# Cortex_Ports.net
KiCad netlist of a schematic drawn in Altium Designer
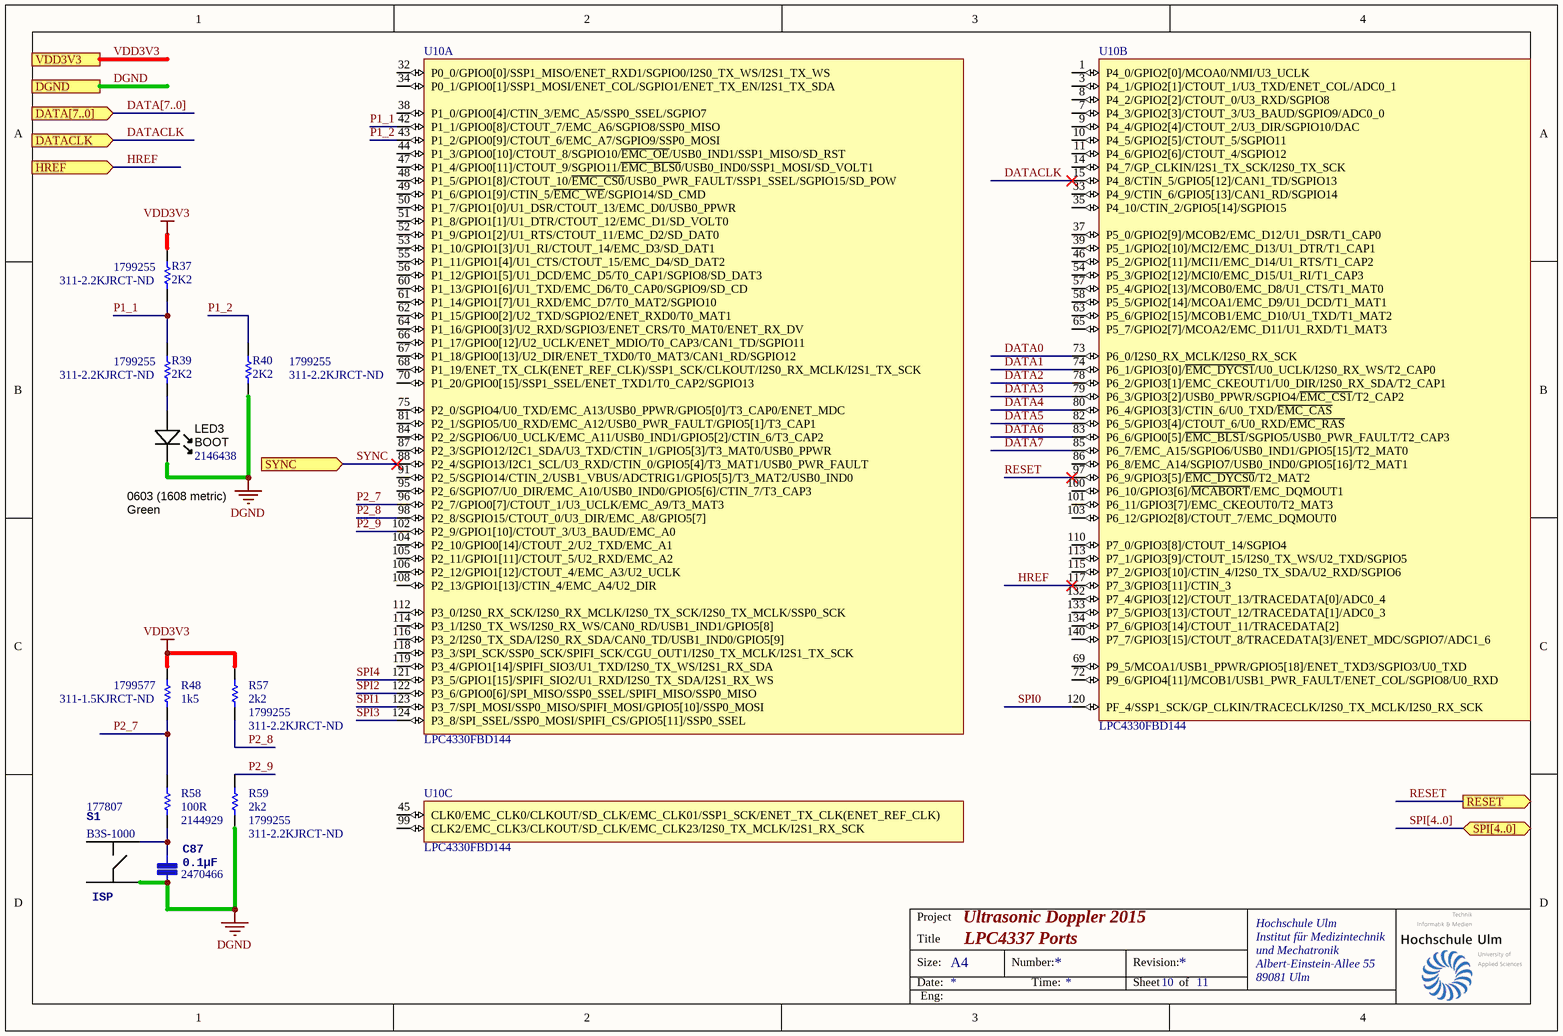
[diagram p0: Cortex_Ports.SchDoc]

(export (version "E")
  (design (tool "Eeschema 10.0.6"))
  (components
    (comp (ref "C87")
      (value "0.1µF")
      (footprint "0402[1005]")
      (description "Cap")
      (fields (field (name "SUPPLIER PART NUMBER 1") "2470466"))
      (libsource (lib "Components") (part "Capacitor"))
    )
    (comp (ref "LED3")
      (value "BOOT")
      (footprint "LED-0603-GREEN")
      (description "LED 0603 SMD Green 525nm 350mcd 20mA")
      (fields
        (field (name "PACKAGE / CASE") "0603 (1608 metric)")
        (field (name "COLOR") "Green")
        (field (name "SUPPLIER PART NUMBER 1") "2146438")
      )
      (libsource (lib "USD Parts") (part "LED_SMD_Green_0603_525nm_350mcd"))
    )
    (comp (ref "R37")
      (value "2K2")
      (footprint "0402[1005]")
      (description "Resistor")
      (fields
        (field (name "SUPPLIER PART NUMBER 1") "311-2.2KJRCT-ND")
        (field (name "SUPPLIER PART NUMBER 2") "1799255")
        (field (name "PUBLISHER") "Altium Limited")
      )
      (libsource (lib "Components") (part "Resistor"))
    )
    (comp (ref "R39")
      (value "2K2")
      (footprint "0402[1005]")
      (description "Resistor")
      (fields
        (field (name "SUPPLIER PART NUMBER 1") "311-2.2KJRCT-ND")
        (field (name "SUPPLIER PART NUMBER 2") "1799255")
        (field (name "PUBLISHER") "Altium Limited")
      )
      (libsource (lib "Components") (part "Resistor"))
    )
    (comp (ref "R40")
      (value "2K2")
      (footprint "0402[1005]")
      (description "Resistor")
      (fields
        (field (name "SUPPLIER PART NUMBER 1") "311-2.2KJRCT-ND")
        (field (name "SUPPLIER PART NUMBER 2") "1799255")
        (field (name "PUBLISHER") "Altium Limited")
      )
      (libsource (lib "Components") (part "Resistor"))
    )
    (comp (ref "R48")
      (value "1k5")
      (footprint "0402[1005]")
      (description "Resistor")
      (fields
        (field (name "SUPPLIER PART NUMBER 1") "311-1.5KJRCT-ND")
        (field (name "SUPPLIER PART NUMBER 2") "1799577")
        (field (name "PUBLISHER") "Altium Limited")
      )
      (libsource (lib "Components") (part "Resistor"))
    )
    (comp (ref "R57")
      (value "2k2")
      (footprint "0402[1005]")
      (description "Resistor")
      (fields
        (field (name "SUPPLIER PART NUMBER 1") "311-2.2KJRCT-ND")
        (field (name "SUPPLIER PART NUMBER 2") "1799255")
        (field (name "PUBLISHER") "Altium Limited")
      )
      (libsource (lib "Components") (part "Resistor"))
    )
    (comp (ref "R58")
      (value "100R")
      (footprint "0402[1005]")
      (description "Resistor")
      (fields (field (name "SUPPLIER PART NUMBER 1") "2144929") (field (name "PUBLISHER") "Altium Limited"))
      (libsource (lib "Components") (part "Resistor"))
    )
    (comp (ref "R59")
      (value "2k2")
      (footprint "0402[1005]")
      (description "Resistor")
      (fields
        (field (name "SUPPLIER PART NUMBER 1") "311-2.2KJRCT-ND")
        (field (name "SUPPLIER PART NUMBER 2") "1799255")
        (field (name "PUBLISHER") "Altium Limited")
      )
      (libsource (lib "Components") (part "Resistor"))
    )
    (comp (ref "S1")
      (value "ISP")
      (footprint "Omron B3S1000")
      (description "Sealed Tactile Switch (SMT)")
      (fields (field (name "ALTIUM_VALUE") "B3S-1000") (field (name "SUPPLIER PART NUMBER 1") "177807"))
      (libsource (lib "USD Parts") (part "B3S-1000"))
    )
    (comp (ref "U10")
      (value "LPC4330FBD144")
      (footprint "LQFP144")
      (libsource (lib "USD Parts") (part "LPC4330FBD144"))
    )
  )
  (nets
    (net (code "1") (name "/DATA0") (class "Default")
      (node (ref "U10") (pin "73") (pinfunction "P6_0/I2S0_RX_MCLK/I2S0_RX_SCK_73") (pintype "bidirectional"))
    )
    (net (code "2") (name "/DATA1") (class "Default")
      (node (ref "U10") (pin "74") (pinfunction "P6_1/GPIO3[0]/~{EMC_DYCS1}/U0_UCLK/I2S0_RX_WS/T2_CAP0_74") (pintype "bidirectional"))
    )
    (net (code "3") (name "/DATA2") (class "Default")
      (node (ref "U10") (pin "78") (pinfunction "P6_2/GPIO3[1]/EMC_CKEOUT1/U0_DIR/I2S0_RX_SDA/T2_CAP1_78") (pintype "bidirectional"))
    )
    (net (code "4") (name "/DATA3") (class "Default")
      (node (ref "U10") (pin "79") (pinfunction "P6_3/GPIO3[2]/USB0_PPWR/SGPIO4/~{EMC_CS1}/T2_CAP2_79") (pintype "bidirectional"))
    )
    (net (code "5") (name "/DATA4") (class "Default")
      (node (ref "U10") (pin "80") (pinfunction "P6_4/GPIO3[3]/CTIN_6/U0_TXD/~{EMC_CAS}_80") (pintype "bidirectional"))
    )
    (net (code "6") (name "/DATA5") (class "Default")
      (node (ref "U10") (pin "82") (pinfunction "P6_5/GPIO3[4]/CTOUT_6/U0_RXD/~{EMC_RAS}_82") (pintype "bidirectional"))
    )
    (net (code "7") (name "/DATA6") (class "Default")
      (node (ref "U10") (pin "83") (pinfunction "P6_6/GPIO0[5]/~{EMC_BLS1}/SGPIO5/USB0_PWR_FAULT/T2_CAP3_83") (pintype "bidirectional"))
    )
    (net (code "8") (name "/DATA7") (class "Default")
      (node (ref "U10") (pin "85") (pinfunction "P6_7/EMC_A15/SGPIO6/USB0_IND1/GPIO5[15]/T2_MAT0_85") (pintype "bidirectional"))
    )
    (net (code "9") (name "/DATACLK") (class "Default")
      (node (ref "U10") (pin "15") (pinfunction "P4_8/CTIN_5/GPIO5[12]/CAN1_TD/SGPIO13_15") (pintype "bidirectional+no_connect"))
    )
    (net (code "11") (name "/HREF") (class "Default")
      (node (ref "U10") (pin "117") (pinfunction "P7_3/GPIO3[11]/CTIN_3_117") (pintype "bidirectional+no_connect"))
    )
    (net (code "12") (name "/P1_1") (class "Default")
      (node (ref "R37") (pin "1") (pinfunction "1_1") (pintype "passive"))
      (node (ref "R39") (pin "1") (pinfunction "1_1") (pintype "passive"))
      (node (ref "U10") (pin "42") (pinfunction "P1_1/GPIO0[8]/CTOUT_7/EMC_A6/SGPIO8/SSP0_MISO_42") (pintype "bidirectional"))
    )
    (net (code "13") (name "/P1_2") (class "Default")
      (node (ref "R40") (pin "1") (pinfunction "1_1") (pintype "passive"))
      (node (ref "U10") (pin "43") (pinfunction "P1_2/GPIO0[9]/CTOUT_6/EMC_A7/SGPIO9/SSP0_MOSI_43") (pintype "bidirectional"))
    )
    (net (code "14") (name "/P2_7") (class "Default")
      (node (ref "R48") (pin "2") (pinfunction "2_2") (pintype "passive"))
      (node (ref "R58") (pin "1") (pinfunction "1_1") (pintype "passive"))
      (node (ref "U10") (pin "96") (pinfunction "P2_7/GPIO0[7]/CTOUT_1/U3_UCLK/EMC_A9/T3_MAT3_96") (pintype "bidirectional"))
    )
    (net (code "15") (name "/P2_8") (class "Default")
      (node (ref "R57") (pin "2") (pinfunction "2_2") (pintype "passive"))
      (node (ref "U10") (pin "98") (pinfunction "P2_8/SGPIO15/CTOUT_0/U3_DIR/EMC_A8/GPIO5[7]_98") (pintype "bidirectional"))
    )
    (net (code "16") (name "/P2_9") (class "Default")
      (node (ref "R59") (pin "1") (pinfunction "1_1") (pintype "passive"))
      (node (ref "U10") (pin "102") (pinfunction "P2_9/GPIO1[10]/CTOUT_3/U3_BAUD/EMC_A0_102") (pintype "bidirectional"))
    )
    (net (code "17") (name "/RESET") (class "Default")
      (node (ref "U10") (pin "97") (pinfunction "P6_9/GPIO3[5]/~{EMC_DYCS0}/T2_MAT2_97") (pintype "bidirectional"))
    )
    (net (code "18") (name "/SPI0") (class "Default")
      (node (ref "U10") (pin "120") (pinfunction "PF_4/SSP1_SCK/GP_CLKIN/TRACECLK/I2S0_TX_MCLK/I2S0_RX_SCK_120") (pintype "bidirectional"))
    )
    (net (code "19") (name "/SPI1") (class "Default")
      (node (ref "U10") (pin "123") (pinfunction "P3_7/SPI_MOSI/SSP0_MISO/SPIFI_MOSI/GPIO5[10]/SSP0_MOSI_123") (pintype "bidirectional"))
    )
    (net (code "20") (name "/SPI2") (class "Default")
      (node (ref "U10") (pin "122") (pinfunction "P3_6/GPIO0[6]/SPI_MISO/SSP0_SSEL/SPIFI_MISO/SSP0_MISO_122") (pintype "bidirectional"))
    )
    (net (code "21") (name "/SPI3") (class "Default")
      (node (ref "U10") (pin "124") (pinfunction "P3_8/SPI_SSEL/SSP0_MOSI/SPIFI_CS/GPIO5[11]/SSP0_SSEL_124") (pintype "bidirectional"))
    )
    (net (code "22") (name "/SPI4") (class "Default")
      (node (ref "U10") (pin "121") (pinfunction "P3_5/GPIO1[15]/SPIFI_SIO2/U1_RXD/I2S0_TX_SDA/I2S1_RX_WS_121") (pintype "bidirectional"))
    )
    (net (code "24") (name "/SYNC") (class "Default")
      (node (ref "U10") (pin "88") (pinfunction "P2_4/SGPIO13/I2C1_SCL/U3_RXD/CTIN_0/GPIO5[4]/T3_MAT1/USB0_PWR_FAULT_88") (pintype "bidirectional+no_connect"))
    )
    (net (code "25") (name "DGND") (class "Default")
      (node (ref "C87") (pin "2") (pinfunction "P$2_2") (pintype "passive"))
      (node (ref "LED3") (pin "K") (pinfunction "K_K") (pintype "passive"))
      (node (ref "R40") (pin "2") (pinfunction "2_2") (pintype "passive"))
      (node (ref "R59") (pin "2") (pinfunction "2_2") (pintype "passive"))
      (node (ref "S1") (pin "1") (pinfunction "1_1") (pintype "passive"))
    )
    (net (code "26") (name "Net-(C87-P$1)") (class "Default")
      (node (ref "C87") (pin "1") (pinfunction "P$1_1") (pintype "passive"))
      (node (ref "R58") (pin "2") (pinfunction "2_2") (pintype "passive"))
      (node (ref "S1") (pin "3") (pinfunction "3_3") (pintype "passive"))
    )
    (net (code "27") (name "Net-(LED3-PadA)") (class "Default")
      (node (ref "LED3") (pin "A") (pinfunction "A_A") (pintype "passive"))
      (node (ref "R39") (pin "2") (pinfunction "2_2") (pintype "passive"))
    )
    (net (code "28") (name "VDD3V3") (class "Default")
      (node (ref "R37") (pin "2") (pinfunction "2_2") (pintype "passive"))
      (node (ref "R48") (pin "1") (pinfunction "1_1") (pintype "passive"))
      (node (ref "R57") (pin "1") (pinfunction "1_1") (pintype "passive"))
    )
    (net (code "29") (name "unconnected-(S1-Pad2)") (class "Default")
      (node (ref "S1") (pin "2") (pinfunction "2_2") (pintype "passive"))
    )
    (net (code "30") (name "unconnected-(S1-Pad4)") (class "Default")
      (node (ref "S1") (pin "4") (pinfunction "4_4") (pintype "passive"))
    )
    (net (code "31") (name "unconnected-(U10A-P0_0{slash}GPIO0[0]{slash}SSP1_MISO{slash}ENET_RXD1{slash}SGPIO0{slash}I2S0_TX_WS{slash}I2S1_TX_WS-Pad32)") (class "Default")
      (node (ref "U10") (pin "32") (pinfunction "P0_0/GPIO0[0]/SSP1_MISO/ENET_RXD1/SGPIO0/I2S0_TX_WS/I2S1_TX_WS_32") (pintype "bidirectional"))
    )
    (net (code "32") (name "unconnected-(U10A-P0_1{slash}GPIO0[1]{slash}SSP1_MOSI{slash}ENET_COL{slash}SGPIO1{slash}ENET_TX_EN{slash}I2S1_TX_SDA-Pad34)") (class "Default")
      (node (ref "U10") (pin "34") (pinfunction "P0_1/GPIO0[1]/SSP1_MOSI/ENET_COL/SGPIO1/ENET_TX_EN/I2S1_TX_SDA_34") (pintype "bidirectional"))
    )
    (net (code "33") (name "unconnected-(U10A-P1_0{slash}GPIO0[4]{slash}CTIN_3{slash}EMC_A5{slash}SSP0_SSEL{slash}SGPIO7-Pad38)") (class "Default")
      (node (ref "U10") (pin "38") (pinfunction "P1_0/GPIO0[4]/CTIN_3/EMC_A5/SSP0_SSEL/SGPIO7_38") (pintype "bidirectional"))
    )
    (net (code "34") (name "unconnected-(U10A-P1_3{slash}GPIO0[10]{slash}CTOUT_8{slash}SGPIO10{slash}~{EMC_OE}{slash}USB0_IND1{slash}SSP1_MISO{slash}SD_RST-Pad44)") (class "Default")
      (node (ref "U10") (pin "44") (pinfunction "P1_3/GPIO0[10]/CTOUT_8/SGPIO10/~{EMC_OE}/USB0_IND1/SSP1_MISO/SD_RST_44") (pintype "bidirectional"))
    )
    (net (code "35") (name "unconnected-(U10A-P1_4{slash}GPIO0[11]{slash}CTOUT_9{slash}SGPIO11{slash}~{EMC_BLS0}{slash}USB0_IND0{slash}SSP1_MOSI{slash}SD_VOLT1-Pad47)") (class "Default")
      (node (ref "U10") (pin "47") (pinfunction "P1_4/GPIO0[11]/CTOUT_9/SGPIO11/~{EMC_BLS0}/USB0_IND0/SSP1_MOSI/SD_VOLT1_47") (pintype "bidirectional"))
    )
    (net (code "36") (name "unconnected-(U10A-P1_5{slash}GPIO1[8]{slash}CTOUT_10{slash}~{EMC_CS0}{slash}USB0_PWR_FAULT{slash}SSP1_SSEL{slash}SGPIO15{slash}SD_POW-Pad48)") (class "Default")
      (node (ref "U10") (pin "48") (pinfunction "P1_5/GPIO1[8]/CTOUT_10/~{EMC_CS0}/USB0_PWR_FAULT/SSP1_SSEL/SGPIO15/SD_POW_48") (pintype "bidirectional"))
    )
    (net (code "37") (name "unconnected-(U10A-P1_6{slash}GPIO1[9]{slash}CTIN_5{slash}~{EMC_WE}{slash}SGPIO14{slash}SD_CMD-Pad49)") (class "Default")
      (node (ref "U10") (pin "49") (pinfunction "P1_6/GPIO1[9]/CTIN_5/~{EMC_WE}/SGPIO14/SD_CMD_49") (pintype "bidirectional"))
    )
    (net (code "38") (name "unconnected-(U10A-P1_7{slash}GPIO1[0]{slash}U1_DSR{slash}CTOUT_13{slash}EMC_D0{slash}USB0_PPWR-Pad50)") (class "Default")
      (node (ref "U10") (pin "50") (pinfunction "P1_7/GPIO1[0]/U1_DSR/CTOUT_13/EMC_D0/USB0_PPWR_50") (pintype "bidirectional"))
    )
    (net (code "39") (name "unconnected-(U10A-P1_8{slash}GPIO1[1]{slash}U1_DTR{slash}CTOUT_12{slash}EMC_D1{slash}SD_VOLT0-Pad51)") (class "Default")
      (node (ref "U10") (pin "51") (pinfunction "P1_8/GPIO1[1]/U1_DTR/CTOUT_12/EMC_D1/SD_VOLT0_51") (pintype "bidirectional"))
    )
    (net (code "40") (name "unconnected-(U10A-P1_9{slash}GPIO1[2]{slash}U1_RTS{slash}CTOUT_11{slash}EMC_D2{slash}SD_DAT0-Pad52)") (class "Default")
      (node (ref "U10") (pin "52") (pinfunction "P1_9/GPIO1[2]/U1_RTS/CTOUT_11/EMC_D2/SD_DAT0_52") (pintype "bidirectional"))
    )
    (net (code "41") (name "unconnected-(U10A-P1_10{slash}GPIO1[3]{slash}U1_RI{slash}CTOUT_14{slash}EMC_D3{slash}SD_DAT1-Pad53)") (class "Default")
      (node (ref "U10") (pin "53") (pinfunction "P1_10/GPIO1[3]/U1_RI/CTOUT_14/EMC_D3/SD_DAT1_53") (pintype "bidirectional"))
    )
    (net (code "42") (name "unconnected-(U10A-P1_11{slash}GPIO1[4]{slash}U1_CTS{slash}CTOUT_15{slash}EMC_D4{slash}SD_DAT2-Pad55)") (class "Default")
      (node (ref "U10") (pin "55") (pinfunction "P1_11/GPIO1[4]/U1_CTS/CTOUT_15/EMC_D4/SD_DAT2_55") (pintype "bidirectional"))
    )
    (net (code "43") (name "unconnected-(U10A-P1_12{slash}GPIO1[5]{slash}U1_DCD{slash}EMC_D5{slash}T0_CAP1{slash}SGPIO8{slash}SD_DAT3-Pad56)") (class "Default")
      (node (ref "U10") (pin "56") (pinfunction "P1_12/GPIO1[5]/U1_DCD/EMC_D5/T0_CAP1/SGPIO8/SD_DAT3_56") (pintype "bidirectional"))
    )
    (net (code "44") (name "unconnected-(U10A-P1_13{slash}GPIO1[6]{slash}U1_TXD{slash}EMC_D6{slash}T0_CAP0{slash}SGPIO9{slash}SD_CD-Pad60)") (class "Default")
      (node (ref "U10") (pin "60") (pinfunction "P1_13/GPIO1[6]/U1_TXD/EMC_D6/T0_CAP0/SGPIO9/SD_CD_60") (pintype "bidirectional"))
    )
    (net (code "45") (name "unconnected-(U10A-P1_14{slash}GPIO1[7]{slash}U1_RXD{slash}EMC_D7{slash}T0_MAT2{slash}SGPIO10-Pad61)") (class "Default")
      (node (ref "U10") (pin "61") (pinfunction "P1_14/GPIO1[7]/U1_RXD/EMC_D7/T0_MAT2/SGPIO10_61") (pintype "bidirectional"))
    )
    (net (code "46") (name "unconnected-(U10A-P1_15{slash}GPIO0[2]{slash}U2_TXD{slash}SGPIO2{slash}ENET_RXD0{slash}T0_MAT1-Pad62)") (class "Default")
      (node (ref "U10") (pin "62") (pinfunction "P1_15/GPIO0[2]/U2_TXD/SGPIO2/ENET_RXD0/T0_MAT1_62") (pintype "bidirectional"))
    )
    (net (code "47") (name "unconnected-(U10A-P1_16{slash}GPIO0[3]{slash}U2_RXD{slash}SGPIO3{slash}ENET_CRS{slash}T0_MAT0{slash}ENET_RX_DV-Pad64)") (class "Default")
      (node (ref "U10") (pin "64") (pinfunction "P1_16/GPIO0[3]/U2_RXD/SGPIO3/ENET_CRS/T0_MAT0/ENET_RX_DV_64") (pintype "bidirectional"))
    )
    (net (code "48") (name "unconnected-(U10A-P1_17{slash}GPIO0[12]{slash}U2_UCLK{slash}ENET_MDIO{slash}T0_CAP3{slash}CAN1_TD{slash}SGPIO11-Pad66)") (class "Default")
      (node (ref "U10") (pin "66") (pinfunction "P1_17/GPIO0[12]/U2_UCLK/ENET_MDIO/T0_CAP3/CAN1_TD/SGPIO11_66") (pintype "bidirectional"))
    )
    (net (code "49") (name "unconnected-(U10A-P1_18{slash}GPIO0[13]{slash}U2_DIR{slash}ENET_TXD0{slash}T0_MAT3{slash}CAN1_RD{slash}SGPIO12-Pad67)") (class "Default")
      (node (ref "U10") (pin "67") (pinfunction "P1_18/GPIO0[13]/U2_DIR/ENET_TXD0/T0_MAT3/CAN1_RD/SGPIO12_67") (pintype "bidirectional"))
    )
    (net (code "50") (name "unconnected-(U10A-P1_19{slash}ENET_TX_CLK(ENET_REF_CLK){slash}SSP1_SCK{slash}CLKOUT{slash}I2S0_RX_MCLK{slash}I2S1_TX_SCK-Pad68)") (class "Default")
      (node (ref "U10") (pin "68") (pinfunction "P1_19/ENET_TX_CLK(ENET_REF_CLK)/SSP1_SCK/CLKOUT/I2S0_RX_MCLK/I2S1_TX_SCK_68") (pintype "bidirectional"))
    )
    (net (code "51") (name "unconnected-(U10A-P1_20{slash}GPIO0[15]{slash}SSP1_SSEL{slash}ENET_TXD1{slash}T0_CAP2{slash}SGPIO13-Pad70)") (class "Default")
      (node (ref "U10") (pin "70") (pinfunction "P1_20/GPIO0[15]/SSP1_SSEL/ENET_TXD1/T0_CAP2/SGPIO13_70") (pintype "bidirectional"))
    )
    (net (code "52") (name "unconnected-(U10A-P2_0{slash}SGPIO4{slash}U0_TXD{slash}EMC_A13{slash}USB0_PPWR{slash}GPIO5[0]{slash}T3_CAP0{slash}ENET_MDC-Pad75)") (class "Default")
      (node (ref "U10") (pin "75") (pinfunction "P2_0/SGPIO4/U0_TXD/EMC_A13/USB0_PPWR/GPIO5[0]/T3_CAP0/ENET_MDC_75") (pintype "bidirectional"))
    )
    (net (code "53") (name "unconnected-(U10A-P2_1{slash}SGPIO5{slash}U0_RXD{slash}EMC_A12{slash}USB0_PWR_FAULT{slash}GPIO5[1]{slash}T3_CAP1-Pad81)") (class "Default")
      (node (ref "U10") (pin "81") (pinfunction "P2_1/SGPIO5/U0_RXD/EMC_A12/USB0_PWR_FAULT/GPIO5[1]/T3_CAP1_81") (pintype "bidirectional"))
    )
    (net (code "54") (name "unconnected-(U10A-P2_2{slash}SGPIO6{slash}U0_UCLK{slash}EMC_A11{slash}USB0_IND1{slash}GPIO5[2]{slash}CTIN_6{slash}T3_CAP2-Pad84)") (class "Default")
      (node (ref "U10") (pin "84") (pinfunction "P2_2/SGPIO6/U0_UCLK/EMC_A11/USB0_IND1/GPIO5[2]/CTIN_6/T3_CAP2_84") (pintype "bidirectional"))
    )
    (net (code "55") (name "unconnected-(U10A-P2_3{slash}SGPIO12{slash}I2C1_SDA{slash}U3_TXD{slash}CTIN_1{slash}GPIO5[3]{slash}T3_MAT0{slash}USB0_PPWR-Pad87)") (class "Default")
      (node (ref "U10") (pin "87") (pinfunction "P2_3/SGPIO12/I2C1_SDA/U3_TXD/CTIN_1/GPIO5[3]/T3_MAT0/USB0_PPWR_87") (pintype "bidirectional"))
    )
    (net (code "56") (name "unconnected-(U10A-P2_5{slash}SGPIO14{slash}CTIN_2{slash}USB1_VBUS{slash}ADCTRIG1{slash}GPIO5[5]{slash}T3_MAT2{slash}USB0_IND0-Pad91)") (class "Default")
      (node (ref "U10") (pin "91") (pinfunction "P2_5/SGPIO14/CTIN_2/USB1_VBUS/ADCTRIG1/GPIO5[5]/T3_MAT2/USB0_IND0_91") (pintype "bidirectional"))
    )
    (net (code "57") (name "unconnected-(U10A-P2_6{slash}SGPIO7{slash}U0_DIR{slash}EMC_A10{slash}USB0_IND0{slash}GPIO5[6]{slash}CTIN_7{slash}T3_CAP3-Pad95)") (class "Default")
      (node (ref "U10") (pin "95") (pinfunction "P2_6/SGPIO7/U0_DIR/EMC_A10/USB0_IND0/GPIO5[6]/CTIN_7/T3_CAP3_95") (pintype "bidirectional"))
    )
    (net (code "58") (name "unconnected-(U10A-P2_10{slash}GPIO0[14]{slash}CTOUT_2{slash}U2_TXD{slash}EMC_A1-Pad104)") (class "Default")
      (node (ref "U10") (pin "104") (pinfunction "P2_10/GPIO0[14]/CTOUT_2/U2_TXD/EMC_A1_104") (pintype "bidirectional"))
    )
    (net (code "59") (name "unconnected-(U10A-P2_11{slash}GPIO1[11]{slash}CTOUT_5{slash}U2_RXD{slash}EMC_A2-Pad105)") (class "Default")
      (node (ref "U10") (pin "105") (pinfunction "P2_11/GPIO1[11]/CTOUT_5/U2_RXD/EMC_A2_105") (pintype "bidirectional"))
    )
    (net (code "60") (name "unconnected-(U10A-P2_12{slash}GPIO1[12]{slash}CTOUT_4{slash}EMC_A3{slash}U2_UCLK-Pad106)") (class "Default")
      (node (ref "U10") (pin "106") (pinfunction "P2_12/GPIO1[12]/CTOUT_4/EMC_A3/U2_UCLK_106") (pintype "bidirectional"))
    )
    (net (code "61") (name "unconnected-(U10A-P2_13{slash}GPIO1[13]{slash}CTIN_4{slash}EMC_A4{slash}U2_DIR-Pad108)") (class "Default")
      (node (ref "U10") (pin "108") (pinfunction "P2_13/GPIO1[13]/CTIN_4/EMC_A4/U2_DIR_108") (pintype "bidirectional"))
    )
    (net (code "62") (name "unconnected-(U10A-P3_0{slash}I2S0_RX_SCK{slash}I2S0_RX_MCLK{slash}I2S0_TX_SCK{slash}I2S0_TX_MCLK{slash}SSP0_SCK-Pad112)") (class "Default")
      (node (ref "U10") (pin "112") (pinfunction "P3_0/I2S0_RX_SCK/I2S0_RX_MCLK/I2S0_TX_SCK/I2S0_TX_MCLK/SSP0_SCK_112") (pintype "bidirectional"))
    )
    (net (code "63") (name "unconnected-(U10A-P3_1{slash}I2S0_TX_WS{slash}I2S0_RX_WS{slash}CAN0_RD{slash}USB1_IND1{slash}GPIO5[8]-Pad114)") (class "Default")
      (node (ref "U10") (pin "114") (pinfunction "P3_1/I2S0_TX_WS/I2S0_RX_WS/CAN0_RD/USB1_IND1/GPIO5[8]_114") (pintype "bidirectional"))
    )
    (net (code "64") (name "unconnected-(U10A-P3_2{slash}I2S0_TX_SDA{slash}I2S0_RX_SDA{slash}CAN0_TD{slash}USB1_IND0{slash}GPIO5[9]-Pad116)") (class "Default")
      (node (ref "U10") (pin "116") (pinfunction "P3_2/I2S0_TX_SDA/I2S0_RX_SDA/CAN0_TD/USB1_IND0/GPIO5[9]_116") (pintype "bidirectional"))
    )
    (net (code "65") (name "unconnected-(U10A-P3_3{slash}SPI_SCK{slash}SSP0_SCK{slash}SPIFI_SCK{slash}CGU_OUT1{slash}I2S0_TX_MCLK{slash}I2S1_TX_SCK-Pad118)") (class "Default")
      (node (ref "U10") (pin "118") (pinfunction "P3_3/SPI_SCK/SSP0_SCK/SPIFI_SCK/CGU_OUT1/I2S0_TX_MCLK/I2S1_TX_SCK_118") (pintype "bidirectional"))
    )
    (net (code "66") (name "unconnected-(U10A-P3_4{slash}GPIO1[14]{slash}SPIFI_SIO3{slash}U1_TXD{slash}I2S0_TX_WS{slash}I2S1_RX_SDA-Pad119)") (class "Default")
      (node (ref "U10") (pin "119") (pinfunction "P3_4/GPIO1[14]/SPIFI_SIO3/U1_TXD/I2S0_TX_WS/I2S1_RX_SDA_119") (pintype "bidirectional"))
    )
    (net (code "67") (name "unconnected-(U10B-P4_0{slash}GPIO2[0]{slash}MCOA0{slash}NMI{slash}U3_UCLK-Pad1)") (class "Default")
      (node (ref "U10") (pin "1") (pinfunction "P4_0/GPIO2[0]/MCOA0/NMI/U3_UCLK_1") (pintype "bidirectional"))
    )
    (net (code "68") (name "unconnected-(U10B-P4_1{slash}GPIO2[1]{slash}CTOUT_1{slash}U3_TXD{slash}ENET_COL{slash}ADC0_1-Pad3)") (class "Default")
      (node (ref "U10") (pin "3") (pinfunction "P4_1/GPIO2[1]/CTOUT_1/U3_TXD/ENET_COL/ADC0_1_3") (pintype "bidirectional"))
    )
    (net (code "69") (name "unconnected-(U10B-P4_2{slash}GPIO2[2]{slash}CTOUT_0{slash}U3_RXD{slash}SGPIO8-Pad8)") (class "Default")
      (node (ref "U10") (pin "8") (pinfunction "P4_2/GPIO2[2]/CTOUT_0/U3_RXD/SGPIO8_8") (pintype "bidirectional"))
    )
    (net (code "70") (name "unconnected-(U10B-P4_3{slash}GPIO2[3]{slash}CTOUT_3{slash}U3_BAUD{slash}SGPIO9{slash}ADC0_0-Pad7)") (class "Default")
      (node (ref "U10") (pin "7") (pinfunction "P4_3/GPIO2[3]/CTOUT_3/U3_BAUD/SGPIO9/ADC0_0_7") (pintype "bidirectional"))
    )
    (net (code "71") (name "unconnected-(U10B-P4_4{slash}GPIO2[4]{slash}CTOUT_2{slash}U3_DIR{slash}SGPIO10{slash}DAC-Pad9)") (class "Default")
      (node (ref "U10") (pin "9") (pinfunction "P4_4/GPIO2[4]/CTOUT_2/U3_DIR/SGPIO10/DAC_9") (pintype "bidirectional"))
    )
    (net (code "72") (name "unconnected-(U10B-P4_5{slash}GPIO2[5]{slash}CTOUT_5{slash}SGPIO11-Pad10)") (class "Default")
      (node (ref "U10") (pin "10") (pinfunction "P4_5/GPIO2[5]/CTOUT_5/SGPIO11_10") (pintype "bidirectional"))
    )
    (net (code "73") (name "unconnected-(U10B-P4_6{slash}GPIO2[6]{slash}CTOUT_4{slash}SGPIO12-Pad11)") (class "Default")
      (node (ref "U10") (pin "11") (pinfunction "P4_6/GPIO2[6]/CTOUT_4/SGPIO12_11") (pintype "bidirectional"))
    )
    (net (code "74") (name "unconnected-(U10B-P4_7{slash}GP_CLKIN{slash}I2S1_TX_SCK{slash}I2S0_TX_SCK-Pad14)") (class "Default")
      (node (ref "U10") (pin "14") (pinfunction "P4_7/GP_CLKIN/I2S1_TX_SCK/I2S0_TX_SCK_14") (pintype "bidirectional"))
    )
    (net (code "75") (name "unconnected-(U10B-P4_9{slash}CTIN_6{slash}GPIO5[13]{slash}CAN1_RD{slash}SGPIO14-Pad33)") (class "Default")
      (node (ref "U10") (pin "33") (pinfunction "P4_9/CTIN_6/GPIO5[13]/CAN1_RD/SGPIO14_33") (pintype "bidirectional"))
    )
    (net (code "76") (name "unconnected-(U10B-P4_10{slash}CTIN_2{slash}GPIO5[14]{slash}SGPIO15-Pad35)") (class "Default")
      (node (ref "U10") (pin "35") (pinfunction "P4_10/CTIN_2/GPIO5[14]/SGPIO15_35") (pintype "bidirectional"))
    )
    (net (code "77") (name "unconnected-(U10B-P5_0{slash}GPIO2[9]{slash}MCOB2{slash}EMC_D12{slash}U1_DSR{slash}T1_CAP0-Pad37)") (class "Default")
      (node (ref "U10") (pin "37") (pinfunction "P5_0/GPIO2[9]/MCOB2/EMC_D12/U1_DSR/T1_CAP0_37") (pintype "bidirectional"))
    )
    (net (code "78") (name "unconnected-(U10B-P5_1{slash}GPIO2[10]{slash}MCI2{slash}EMC_D13{slash}U1_DTR{slash}T1_CAP1-Pad39)") (class "Default")
      (node (ref "U10") (pin "39") (pinfunction "P5_1/GPIO2[10]/MCI2/EMC_D13/U1_DTR/T1_CAP1_39") (pintype "bidirectional"))
    )
    (net (code "79") (name "unconnected-(U10B-P5_2{slash}GPIO2[11]{slash}MCI1{slash}EMC_D14{slash}U1_RTS{slash}T1_CAP2-Pad46)") (class "Default")
      (node (ref "U10") (pin "46") (pinfunction "P5_2/GPIO2[11]/MCI1/EMC_D14/U1_RTS/T1_CAP2_46") (pintype "bidirectional"))
    )
    (net (code "80") (name "unconnected-(U10B-P5_3{slash}GPIO2[12]{slash}MCI0{slash}EMC_D15{slash}U1_RI{slash}T1_CAP3-Pad54)") (class "Default")
      (node (ref "U10") (pin "54") (pinfunction "P5_3/GPIO2[12]/MCI0/EMC_D15/U1_RI/T1_CAP3_54") (pintype "bidirectional"))
    )
    (net (code "81") (name "unconnected-(U10B-P5_4{slash}GPIO2[13]{slash}MCOB0{slash}EMC_D8{slash}U1_CTS{slash}T1_MAT0-Pad57)") (class "Default")
      (node (ref "U10") (pin "57") (pinfunction "P5_4/GPIO2[13]/MCOB0/EMC_D8/U1_CTS/T1_MAT0_57") (pintype "bidirectional"))
    )
    (net (code "82") (name "unconnected-(U10B-P5_5{slash}GPIO2[14]{slash}MCOA1{slash}EMC_D9{slash}U1_DCD{slash}T1_MAT1-Pad58)") (class "Default")
      (node (ref "U10") (pin "58") (pinfunction "P5_5/GPIO2[14]/MCOA1/EMC_D9/U1_DCD/T1_MAT1_58") (pintype "bidirectional"))
    )
    (net (code "83") (name "unconnected-(U10B-P5_6{slash}GPIO2[15]{slash}MCOB1{slash}EMC_D10{slash}U1_TXD{slash}T1_MAT2-Pad63)") (class "Default")
      (node (ref "U10") (pin "63") (pinfunction "P5_6/GPIO2[15]/MCOB1/EMC_D10/U1_TXD/T1_MAT2_63") (pintype "bidirectional"))
    )
    (net (code "84") (name "unconnected-(U10B-P5_7{slash}GPIO2[7]{slash}MCOA2{slash}EMC_D11{slash}U1_RXD{slash}T1_MAT3-Pad65)") (class "Default")
      (node (ref "U10") (pin "65") (pinfunction "P5_7/GPIO2[7]/MCOA2/EMC_D11/U1_RXD/T1_MAT3_65") (pintype "bidirectional"))
    )
    (net (code "85") (name "unconnected-(U10B-P6_8{slash}EMC_A14{slash}SGPIO7{slash}USB0_IND0{slash}GPIO5[16]{slash}T2_MAT1-Pad86)") (class "Default")
      (node (ref "U10") (pin "86") (pinfunction "P6_8/EMC_A14/SGPIO7/USB0_IND0/GPIO5[16]/T2_MAT1_86") (pintype "bidirectional"))
    )
    (net (code "86") (name "unconnected-(U10B-P6_10{slash}GPIO3[6]{slash}~{MCABORT}{slash}EMC_DQMOUT1-Pad100)") (class "Default")
      (node (ref "U10") (pin "100") (pinfunction "P6_10/GPIO3[6]/~{MCABORT}/EMC_DQMOUT1_100") (pintype "bidirectional"))
    )
    (net (code "87") (name "unconnected-(U10B-P6_11{slash}GPIO3[7]{slash}EMC_CKEOUT0{slash}T2_MAT3-Pad101)") (class "Default")
      (node (ref "U10") (pin "101") (pinfunction "P6_11/GPIO3[7]/EMC_CKEOUT0/T2_MAT3_101") (pintype "bidirectional"))
    )
    (net (code "88") (name "unconnected-(U10B-P6_12{slash}GPIO2[8]{slash}CTOUT_7{slash}EMC_DQMOUT0-Pad103)") (class "Default")
      (node (ref "U10") (pin "103") (pinfunction "P6_12/GPIO2[8]/CTOUT_7/EMC_DQMOUT0_103") (pintype "bidirectional"))
    )
    (net (code "89") (name "unconnected-(U10B-P7_0{slash}GPIO3[8]{slash}CTOUT_14{slash}SGPIO4-Pad110)") (class "Default")
      (node (ref "U10") (pin "110") (pinfunction "P7_0/GPIO3[8]/CTOUT_14/SGPIO4_110") (pintype "bidirectional"))
    )
    (net (code "90") (name "unconnected-(U10B-P7_1{slash}GPIO3[9]{slash}CTOUT_15{slash}I2S0_TX_WS{slash}U2_TXD{slash}SGPIO5-Pad113)") (class "Default")
      (node (ref "U10") (pin "113") (pinfunction "P7_1/GPIO3[9]/CTOUT_15/I2S0_TX_WS/U2_TXD/SGPIO5_113") (pintype "bidirectional"))
    )
    (net (code "91") (name "unconnected-(U10B-P7_2{slash}GPIO3[10]{slash}CTIN_4{slash}I2S0_TX_SDA{slash}U2_RXD{slash}SGPIO6-Pad115)") (class "Default")
      (node (ref "U10") (pin "115") (pinfunction "P7_2/GPIO3[10]/CTIN_4/I2S0_TX_SDA/U2_RXD/SGPIO6_115") (pintype "bidirectional"))
    )
    (net (code "92") (name "unconnected-(U10B-P7_4{slash}GPIO3[12]{slash}CTOUT_13{slash}TRACEDATA[0]{slash}ADC0_4-Pad132)") (class "Default")
      (node (ref "U10") (pin "132") (pinfunction "P7_4/GPIO3[12]/CTOUT_13/TRACEDATA[0]/ADC0_4_132") (pintype "bidirectional"))
    )
    (net (code "93") (name "unconnected-(U10B-P7_5{slash}GPIO3[13]{slash}CTOUT_12{slash}TRACEDATA[1]{slash}ADC0_3-Pad133)") (class "Default")
      (node (ref "U10") (pin "133") (pinfunction "P7_5/GPIO3[13]/CTOUT_12/TRACEDATA[1]/ADC0_3_133") (pintype "bidirectional"))
    )
    (net (code "94") (name "unconnected-(U10B-P7_6{slash}GPIO3[14]{slash}CTOUT_11{slash}TRACEDATA[2]-Pad134)") (class "Default")
      (node (ref "U10") (pin "134") (pinfunction "P7_6/GPIO3[14]/CTOUT_11/TRACEDATA[2]_134") (pintype "bidirectional"))
    )
    (net (code "95") (name "unconnected-(U10B-P7_7{slash}GPIO3[15]{slash}CTOUT_8{slash}TRACEDATA[3]{slash}ENET_MDC{slash}SGPIO7{slash}ADC1_6-Pad140)") (class "Default")
      (node (ref "U10") (pin "140") (pinfunction "P7_7/GPIO3[15]/CTOUT_8/TRACEDATA[3]/ENET_MDC/SGPIO7/ADC1_6_140") (pintype "bidirectional"))
    )
    (net (code "96") (name "unconnected-(U10B-P9_5{slash}MCOA1{slash}USB1_PPWR{slash}GPIO5[18]{slash}ENET_TXD3{slash}SGPIO3{slash}U0_TXD-Pad69)") (class "Default")
      (node (ref "U10") (pin "69") (pinfunction "P9_5/MCOA1/USB1_PPWR/GPIO5[18]/ENET_TXD3/SGPIO3/U0_TXD_69") (pintype "bidirectional"))
    )
    (net (code "97") (name "unconnected-(U10B-P9_6{slash}GPIO4[11]{slash}MCOB1{slash}USB1_PWR_FAULT{slash}ENET_COL{slash}SGPIO8{slash}U0_RXD-Pad72)") (class "Default")
      (node (ref "U10") (pin "72") (pinfunction "P9_6/GPIO4[11]/MCOB1/USB1_PWR_FAULT/ENET_COL/SGPIO8/U0_RXD_72") (pintype "bidirectional"))
    )
    (net (code "98") (name "unconnected-(U10C-CLK0{slash}EMC_CLK0{slash}CLKOUT{slash}SD_CLK{slash}EMC_CLK01{slash}SSP1_SCK{slash}ENET_TX_CLK(ENET_REF_CLK)-Pad45)") (class "Default")
      (node (ref "U10") (pin "45") (pinfunction "CLK0/EMC_CLK0/CLKOUT/SD_CLK/EMC_CLK01/SSP1_SCK/ENET_TX_CLK(ENET_REF_CLK)_45") (pintype "bidirectional"))
    )
    (net (code "99") (name "unconnected-(U10C-CLK2{slash}EMC_CLK3{slash}CLKOUT{slash}SD_CLK{slash}EMC_CLK23{slash}I2S0_TX_MCLK{slash}I2S1_RX_SCK-Pad99)") (class "Default")
      (node (ref "U10") (pin "99") (pinfunction "CLK2/EMC_CLK3/CLKOUT/SD_CLK/EMC_CLK23/I2S0_TX_MCLK/I2S1_RX_SCK_99") (pintype "bidirectional"))
    )
  )
)
